# AD_PCB_EXTERNA.net
KiCad netlist of a schematic drawn in Altium Designer
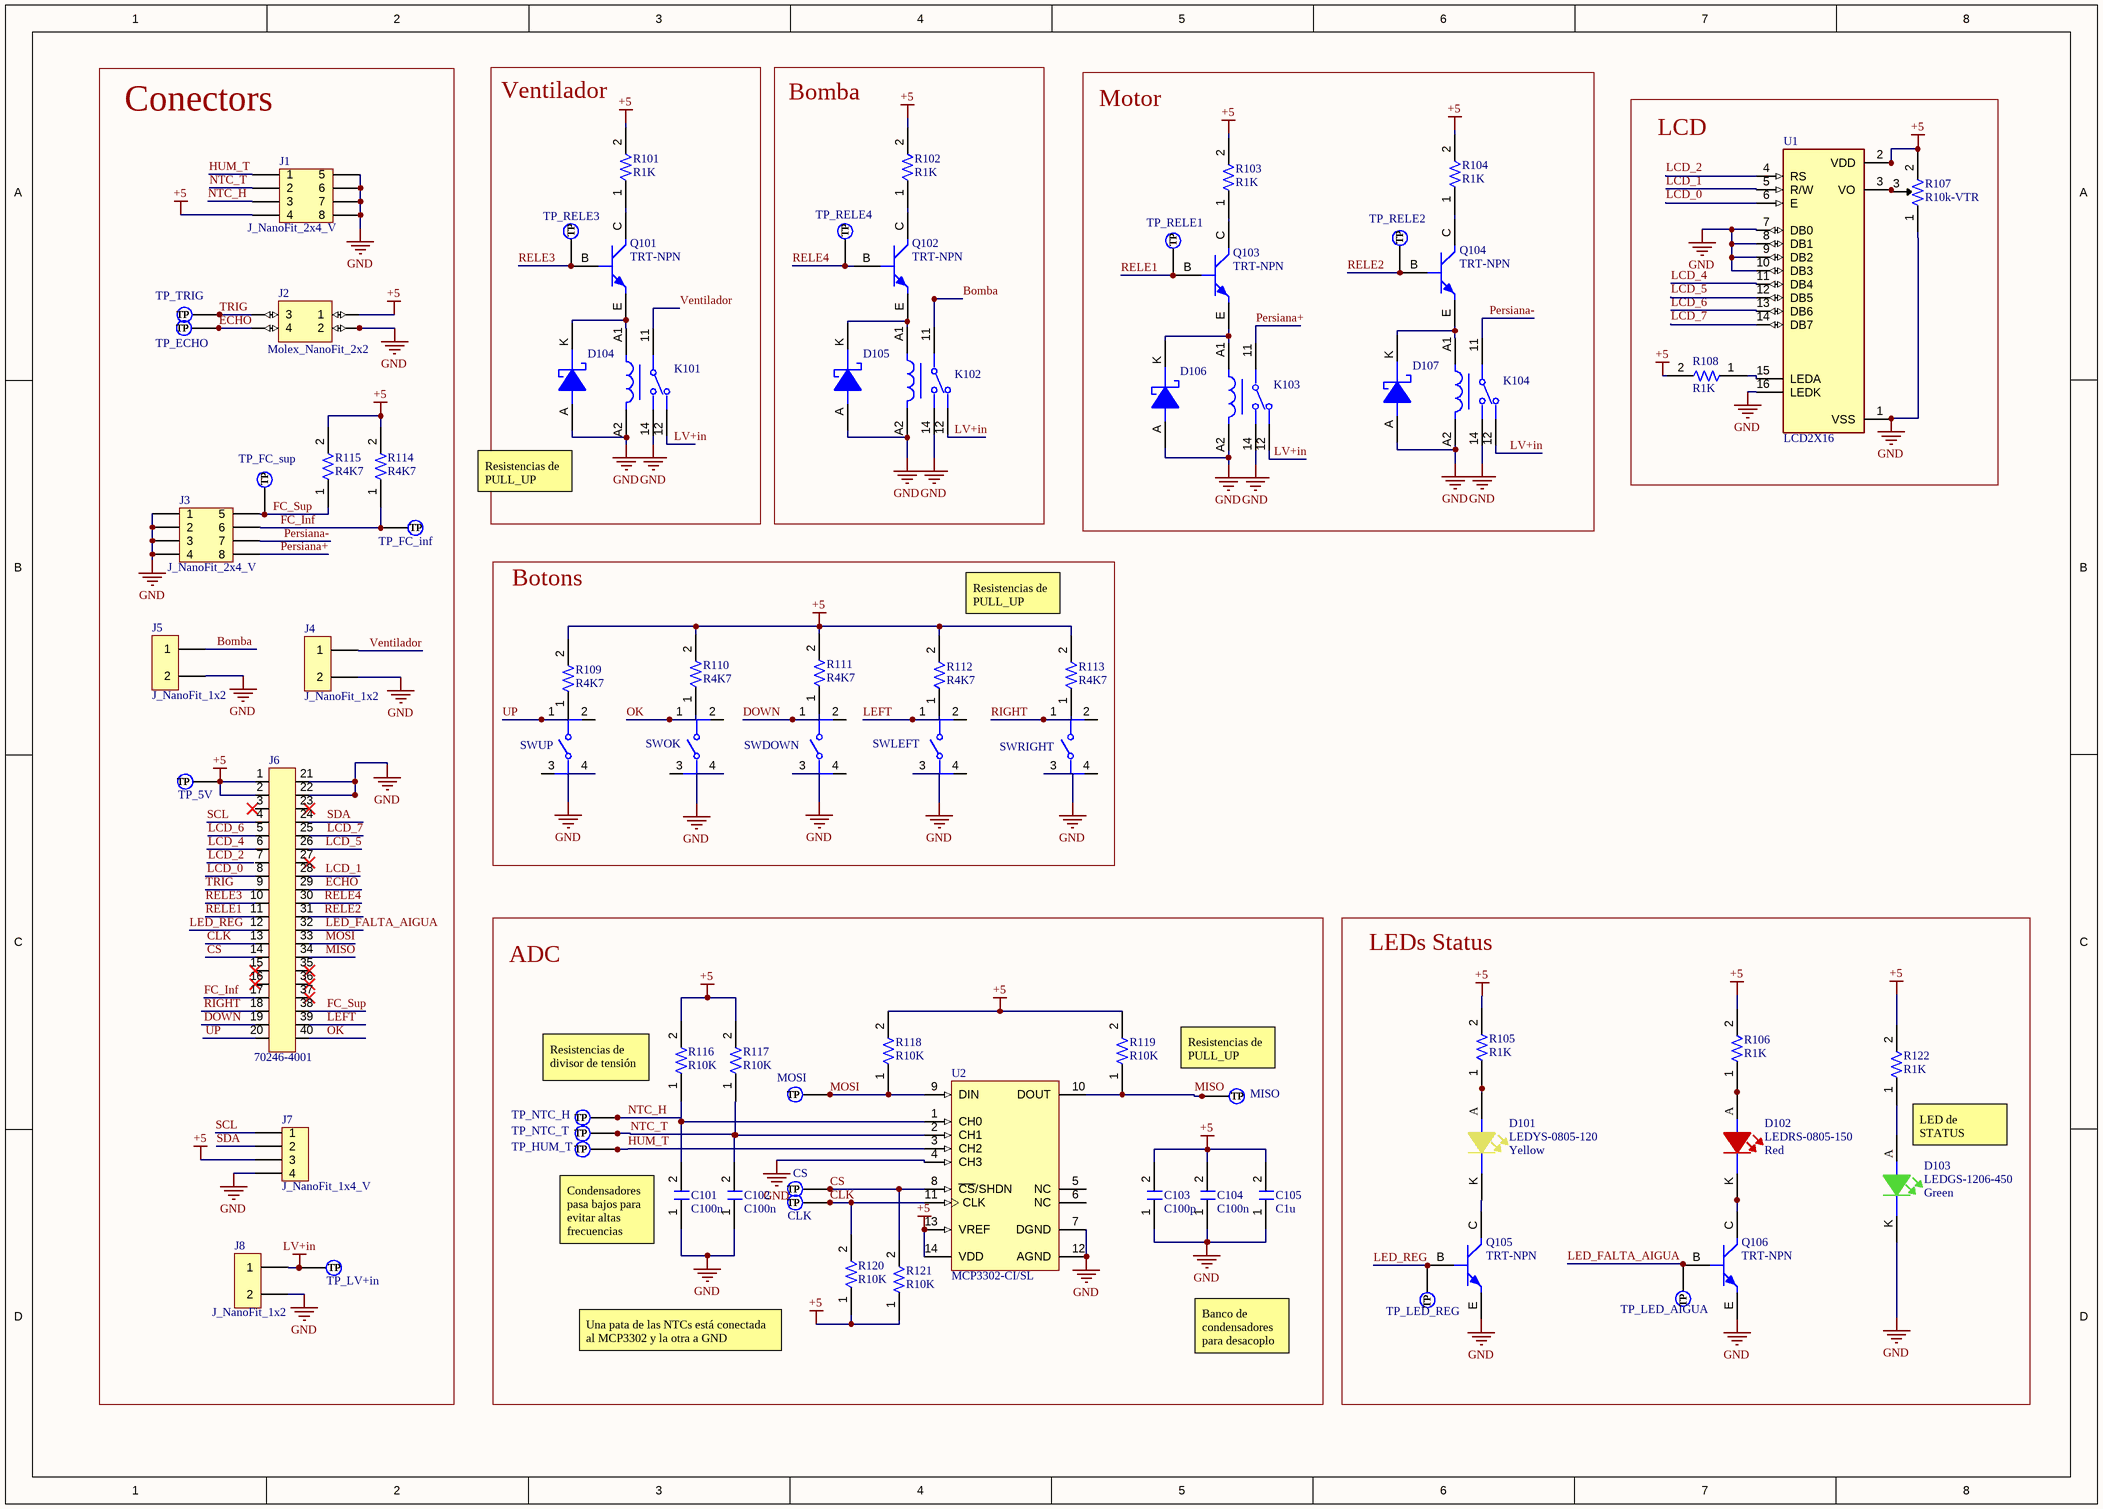
[diagram p0: AD_PCB_EXTERNA.SchDoc]

(export (version "E")
  (design (tool "Eeschema 10.0.6"))
  (components
    (comp (ref "C101")
      (value "C100n")
      (footprint "C0805FNPC-R")
      (description "Cap, 0.1ΜF, 50V, 10%, X7R, 0805")
      (fields (field (name "TOLERANCE") "10%") (field (name ".CREATOR") "DR"))
      (libsource (lib "EMEA- E-Tech Racing- I'Escola d'Enginyeria de Barcelona Est") (part "C100p-50V-0805FNPC-C0G/NP0"))
    )
    (comp (ref "C102")
      (value "C100n")
      (footprint "C0805FNPC-R")
      (description "Cap, 0.1ΜF, 50V, 10%, X7R, 0805")
      (fields (field (name "TOLERANCE") "10%") (field (name ".CREATOR") "DR"))
      (libsource (lib "EMEA- E-Tech Racing- I'Escola d'Enginyeria de Barcelona Est") (part "C100p-50V-0805FNPC-C0G/NP0"))
    )
    (comp (ref "C103")
      (value "C100p")
      (footprint "C0805FNPC-W")
      (fields
        (field (name "MANUFACTURER") "Wurth Electronics")
        (field (name "TOLERANCE") "5%")
        (field (name "MANUFACTURER PART NUMBER") "885012007057")
        (field (name ".CREATOR") "DR")
      )
      (libsource (lib "EMEA- E-Tech Racing- I'Escola d'Enginyeria de Barcelona Est") (part "C100p-50V-0805FNPC-C0G/NP0"))
    )
    (comp (ref "C104")
      (value "C100n")
      (footprint "C0805FNPC-R")
      (description "Cap, 0.1ΜF, 50V, 10%, X7R, 0805")
      (fields (field (name "TOLERANCE") "10%") (field (name ".CREATOR") "DR"))
      (libsource (lib "EMEA- E-Tech Racing- I'Escola d'Enginyeria de Barcelona Est") (part "C100p-50V-0805FNPC-C0G/NP0"))
    )
    (comp (ref "C105")
      (value "C1u")
      (footprint "C0805FNPC-R")
      (fields (field (name "TOLERANCE") "10%") (field (name ".CREATOR") "GP"))
      (libsource (lib "EMEA- E-Tech Racing- I'Escola d'Enginyeria de Barcelona Est") (part "C1u"))
    )
    (comp (ref "CLK")
      (value "TestPoint")
      (footprint "TestPoint")
      (description "Test Point 1x1 mm")
      (fields (field (name ".PCBCHECK") "GP") (field (name ".CREATOR") "GP") (field (name ".SCHCHECK") "GP"))
      (libsource (lib "EMEA- E-Tech Racing- I'Escola d'Enginyeria de Barcelona Est") (part "TestPoint"))
    )
    (comp (ref "CS")
      (value "TestPoint")
      (footprint "TestPoint")
      (description "Test Point 1x1 mm")
      (fields (field (name ".PCBCHECK") "GP") (field (name ".CREATOR") "GP") (field (name ".SCHCHECK") "GP"))
      (libsource (lib "EMEA- E-Tech Racing- I'Escola d'Enginyeria de Barcelona Est") (part "TestPoint"))
    )
    (comp (ref "D101")
      (value "LEDYS-0805-120")
      (footprint "LED_0805_WE")
      (description "2 V Yellow LED 2012 (0805) SMD, Wurth Elektronik WL-SMCW 150080YS75000")
      (fields (field (name "COLOR") "Yellow") (field (name ".CREATOR") "DR"))
      (libsource (lib "EMEA- E-Tech Racing- I'Escola d'Enginyeria de Barcelona Est") (part "LEDYS-3528-260"))
    )
    (comp (ref "D102")
      (value "LEDRS-0805-150")
      (footprint "LED_0805_WE")
      (description "0805(H=0.8mm) 红色 高亮 λD=625nm VF=2V IF=30mA PD=72mW")
      (fields (field (name "COLOR") "Red") (field (name ".CREATOR") "DR"))
      (libsource (lib "EMEA- E-Tech Racing- I'Escola d'Enginyeria de Barcelona Est") (part "LEDRS-1206-1100-Reverse"))
    )
    (comp (ref "D103")
      (value "LEDGS-1206-450")
      (footprint "LED_1206_WE")
      (description "Led, Green, 520 Nm, 3.2 V, 30 Ma, 450 Mcd Rohs Compliant: Yes")
      (fields
        (field (name "COLOR") "Green")
        (field (name "MANUFACTURER") "Wurth Electronics")
        (field (name "MANUFACTURER PART NUMBER") "150120GS75000")
        (field (name ".CREATOR") "GP")
      )
      (libsource (lib "EMEA- E-Tech Racing- I'Escola d'Enginyeria de Barcelona Est") (part "LEDGS-2214-1200"))
    )
    (comp (ref "D104")
      (value "DSC-0.5/30-SOD123")
      (footprint "DSC-SOD123")
      (description "VR=30V IF=500mA 30pF P=410mW")
      (fields (field (name ".CREATOR") "GP"))
      (libsource (lib "EMEA- E-Tech Racing- I'Escola d'Enginyeria de Barcelona Est") (part "DSC-0.5/30-SOD123"))
    )
    (comp (ref "D105")
      (value "DSC-0.5/30-SOD123")
      (footprint "DSC-SOD123")
      (description "VR=30V IF=500mA 30pF P=410mW")
      (fields (field (name ".CREATOR") "GP"))
      (libsource (lib "EMEA- E-Tech Racing- I'Escola d'Enginyeria de Barcelona Est") (part "DSC-0.5/30-SOD123"))
    )
    (comp (ref "D106")
      (value "DSC-0.5/30-SOD123")
      (footprint "DSC-SOD123")
      (description "VR=30V IF=500mA 30pF P=410mW")
      (fields (field (name ".CREATOR") "GP"))
      (libsource (lib "EMEA- E-Tech Racing- I'Escola d'Enginyeria de Barcelona Est") (part "DSC-0.5/30-SOD123"))
    )
    (comp (ref "D107")
      (value "DSC-0.5/30-SOD123")
      (footprint "DSC-SOD123")
      (description "VR=30V IF=500mA 30pF P=410mW")
      (fields (field (name ".CREATOR") "GP"))
      (libsource (lib "EMEA- E-Tech Racing- I'Escola d'Enginyeria de Barcelona Est") (part "DSC-0.5/30-SOD123"))
    )
    (comp (ref "J1")
      (value "J_NanoFit_2x4_V")
      (footprint "J_NanoFit_2x4_V")
      (description "Nano-Fit Conn Power HDR 8 POS 2.5mm Solder ST Thru-Hole 8 Terminal 1 Port Nano-Fit™ Frame")
      (fields (field (name "MANUFACTURER") "Molex") (field (name "MANUFACTURER PART NUMBER") "105310-1108"))
      (libsource (lib "EMEA- E-Tech Racing- I'Escola d'Enginyeria de Barcelona Est") (part "J_NanoFit_2x4_V"))
    )
    (comp (ref "J2")
      (value "Molex_NanoFit_2x2")
      (footprint "J_NanoFit_2x2_V")
      (description "Nano-Fit Vertical Header Through Hole 2.50mm Pitch Dual Row 4 Circuits Tin (Sn) Plating Black")
      (fields
        (field (name "MANUFACTURER") "Molex")
        (field (name "MANUFACTURER PART NUMBER") "1053141104")
        (field (name ".CREATOR") "GP")
      )
      (libsource (lib "EMEA- E-Tech Racing- I'Escola d'Enginyeria de Barcelona Est") (part "J_Nanofit_2x2"))
    )
    (comp (ref "J3")
      (value "J_NanoFit_2x4_V")
      (footprint "J_NanoFit_2x4_V")
      (description "Nano-Fit Conn Power HDR 8 POS 2.5mm Solder ST Thru-Hole 8 Terminal 1 Port Nano-Fit™ Frame")
      (fields (field (name "MANUFACTURER") "Molex") (field (name "MANUFACTURER PART NUMBER") "105310-1108"))
      (libsource (lib "EMEA- E-Tech Racing- I'Escola d'Enginyeria de Barcelona Est") (part "J_NanoFit_2x4_V"))
    )
    (comp (ref "J4")
      (value "J_NanoFit_1x2")
      (footprint "FP-105309-1102-MFG")
      (description "Conn HDR 2 POS 2.5mm Solder ST Thru-Hole 2 Terminal 1 Port Nano-Fit Tray")
      (libsource (lib "EMEA- E-Tech Racing- I'Escola d'Enginyeria de Barcelona Est") (part "Molex Nano-Fit"))
    )
    (comp (ref "J5")
      (value "J_NanoFit_1x2")
      (footprint "FP-105309-1102-MFG")
      (description "Conn HDR 2 POS 2.5mm Solder ST Thru-Hole 2 Terminal 1 Port Nano-Fit Tray")
      (libsource (lib "EMEA- E-Tech Racing- I'Escola d'Enginyeria de Barcelona Est") (part "Molex Nano-Fit"))
    )
    (comp (ref "J6")
      (value "70246-4001")
      (footprint "CONN_7024640xx_MOL")
      (libsource (lib "EMEA- E-Tech Racing- I'Escola d'Enginyeria de Barcelona Est") (part "70246-4001-Symbol-1"))
    )
    (comp (ref "J7")
      (value "J_NanoFit_1x4_V")
      (footprint "J_NanoFit_1x4_V")
      (description "Nano-Fit Vertical Header Through Hole 2.50mm Pitch Single Row 4 Circuits with Kinked Pins 0.38")
      (fields (field (name ".CREATOR") "DO"))
      (libsource (lib "EMEA- E-Tech Racing- I'Escola d'Enginyeria de Barcelona Est") (part "J_NanoFit_1x4_V_W"))
    )
    (comp (ref "J8")
      (value "J_NanoFit_1x2")
      (footprint "FP-105309-1102-MFG")
      (description "Conn HDR 2 POS 2.5mm Solder ST Thru-Hole 2 Terminal 1 Port Nano-Fit Tray")
      (libsource (lib "EMEA- E-Tech Racing- I'Escola d'Enginyeria de Barcelona Est") (part "Molex Nano-Fit"))
    )
    (comp (ref "K101")
      (value "Relay_RZ01-1C4-D005")
      (footprint "FP-1415899-7-MFG")
      (libsource (lib "EMEA- E-Tech Racing- I'Escola d'Enginyeria de Barcelona Est") (part "5e088b4eeede5deee4b60b77e0ea9e2"))
    )
    (comp (ref "K102")
      (value "Relay_RZ01-1C4-D005")
      (footprint "FP-1415899-7-MFG")
      (libsource (lib "EMEA- E-Tech Racing- I'Escola d'Enginyeria de Barcelona Est") (part "5e088b4eeede5deee4b60b77e0ea9e2"))
    )
    (comp (ref "K103")
      (value "Relay_RZ01-1C4-D005")
      (footprint "FP-1415899-7-MFG")
      (libsource (lib "EMEA- E-Tech Racing- I'Escola d'Enginyeria de Barcelona Est") (part "5e088b4eeede5deee4b60b77e0ea9e2"))
    )
    (comp (ref "K104")
      (value "Relay_RZ01-1C4-D005")
      (footprint "FP-1415899-7-MFG")
      (libsource (lib "EMEA- E-Tech Racing- I'Escola d'Enginyeria de Barcelona Est") (part "5e088b4eeede5deee4b60b77e0ea9e2"))
    )
    (comp (ref "MISO")
      (value "TestPoint")
      (footprint "TestPoint")
      (description "Test Point 1x1 mm")
      (fields (field (name ".PCBCHECK") "GP") (field (name ".CREATOR") "GP") (field (name ".SCHCHECK") "GP"))
      (libsource (lib "EMEA- E-Tech Racing- I'Escola d'Enginyeria de Barcelona Est") (part "TestPoint"))
    )
    (comp (ref "MOSI")
      (value "TestPoint")
      (footprint "TestPoint")
      (description "Test Point 1x1 mm")
      (fields (field (name ".PCBCHECK") "GP") (field (name ".CREATOR") "GP") (field (name ".SCHCHECK") "GP"))
      (libsource (lib "EMEA- E-Tech Racing- I'Escola d'Enginyeria de Barcelona Est") (part "TestPoint"))
    )
    (comp (ref "Q101")
      (value "TRT-NPN")
      (footprint "TRT-NPN-0.5/45-SOT23")
      (description "ON Semi BC817-25LT1G NPN Bipolar Transistor; 0.5 A; 45 V; 3-Pin SOT-23")
      (fields (field (name ".CREATOR") "GP"))
      (libsource (lib "EMEA- E-Tech Racing- I'Escola d'Enginyeria de Barcelona Est") (part "TRT-NPN-0.5/45-SOT23"))
    )
    (comp (ref "Q102")
      (value "TRT-NPN")
      (footprint "TRT-NPN-0.5/45-SOT23")
      (description "ON Semi BC817-25LT1G NPN Bipolar Transistor; 0.5 A; 45 V; 3-Pin SOT-23")
      (fields (field (name ".CREATOR") "GP"))
      (libsource (lib "EMEA- E-Tech Racing- I'Escola d'Enginyeria de Barcelona Est") (part "TRT-NPN-0.5/45-SOT23"))
    )
    (comp (ref "Q103")
      (value "TRT-NPN")
      (footprint "TRT-NPN-0.5/45-SOT23")
      (description "ON Semi BC817-25LT1G NPN Bipolar Transistor; 0.5 A; 45 V; 3-Pin SOT-23")
      (fields (field (name ".CREATOR") "GP"))
      (libsource (lib "EMEA- E-Tech Racing- I'Escola d'Enginyeria de Barcelona Est") (part "TRT-NPN-0.5/45-SOT23"))
    )
    (comp (ref "Q104")
      (value "TRT-NPN")
      (footprint "TRT-NPN-0.5/45-SOT23")
      (description "ON Semi BC817-25LT1G NPN Bipolar Transistor; 0.5 A; 45 V; 3-Pin SOT-23")
      (fields (field (name ".CREATOR") "GP"))
      (libsource (lib "EMEA- E-Tech Racing- I'Escola d'Enginyeria de Barcelona Est") (part "TRT-NPN-0.5/45-SOT23"))
    )
    (comp (ref "Q105")
      (value "TRT-NPN")
      (footprint "TRT-NPN-0.5/45-SOT23")
      (description "ON Semi BC817-25LT1G NPN Bipolar Transistor; 0.5 A; 45 V; 3-Pin SOT-23")
      (fields (field (name ".CREATOR") "GP"))
      (libsource (lib "EMEA- E-Tech Racing- I'Escola d'Enginyeria de Barcelona Est") (part "TRT-NPN-0.5/45-SOT23"))
    )
    (comp (ref "Q106")
      (value "TRT-NPN")
      (footprint "TRT-NPN-0.5/45-SOT23")
      (description "ON Semi BC817-25LT1G NPN Bipolar Transistor; 0.5 A; 45 V; 3-Pin SOT-23")
      (fields (field (name ".CREATOR") "GP"))
      (libsource (lib "EMEA- E-Tech Racing- I'Escola d'Enginyeria de Barcelona Est") (part "TRT-NPN-0.5/45-SOT23"))
    )
    (comp (ref "R101")
      (value "R1K")
      (footprint "0805")
      (description "Fixed Resistor, Thin Film, 0.125W, 1000ohm, 150V, 0.1% +/-Tol, 15ppm/Cel, Surface Mount, 0805")
      (fields (field (name "TOLERANCE") "0.1%") (field (name "POWER") "125mW"))
      (libsource (lib "EMEA- E-Tech Racing- I'Escola d'Enginyeria de Barcelona Est") (part "CRCW08055K30FKTA"))
    )
    (comp (ref "R102")
      (value "R1K")
      (footprint "0805")
      (description "Fixed Resistor, Thin Film, 0.125W, 1000ohm, 150V, 0.1% +/-Tol, 15ppm/Cel, Surface Mount, 0805")
      (fields (field (name "TOLERANCE") "0.1%") (field (name "POWER") "125mW"))
      (libsource (lib "EMEA- E-Tech Racing- I'Escola d'Enginyeria de Barcelona Est") (part "CRCW08055K30FKTA"))
    )
    (comp (ref "R103")
      (value "R1K")
      (footprint "0805")
      (description "Fixed Resistor, Thin Film, 0.125W, 1000ohm, 150V, 0.1% +/-Tol, 15ppm/Cel, Surface Mount, 0805")
      (fields (field (name "TOLERANCE") "0.1%") (field (name "POWER") "125mW"))
      (libsource (lib "EMEA- E-Tech Racing- I'Escola d'Enginyeria de Barcelona Est") (part "CRCW08055K30FKTA"))
    )
    (comp (ref "R104")
      (value "R1K")
      (footprint "0805")
      (description "Fixed Resistor, Thin Film, 0.125W, 1000ohm, 150V, 0.1% +/-Tol, 15ppm/Cel, Surface Mount, 0805")
      (fields (field (name "TOLERANCE") "0.1%") (field (name "POWER") "125mW"))
      (libsource (lib "EMEA- E-Tech Racing- I'Escola d'Enginyeria de Barcelona Est") (part "CRCW08055K30FKTA"))
    )
    (comp (ref "R105")
      (value "R1K")
      (footprint "0805")
      (description "Fixed Resistor, Thin Film, 0.125W, 1000ohm, 150V, 0.1% +/-Tol, 15ppm/Cel, Surface Mount, 0805")
      (fields (field (name "TOLERANCE") "0.1%") (field (name "POWER") "125mW"))
      (libsource (lib "EMEA- E-Tech Racing- I'Escola d'Enginyeria de Barcelona Est") (part "CRCW08055K30FKTA"))
    )
    (comp (ref "R106")
      (value "R1K")
      (footprint "0805")
      (description "Fixed Resistor, Thin Film, 0.125W, 1000ohm, 150V, 0.1% +/-Tol, 15ppm/Cel, Surface Mount, 0805")
      (fields (field (name "TOLERANCE") "0.1%") (field (name "POWER") "125mW"))
      (libsource (lib "EMEA- E-Tech Racing- I'Escola d'Enginyeria de Barcelona Est") (part "CRCW08055K30FKTA"))
    )
    (comp (ref "R107")
      (value "R10k-VTR")
      (footprint "R10k-VTR")
      (description "Trimmer, Cermet, Rest 10 Kilohms, PCB, 25 Turns, Pwr-Rtg 0.5W, 3296 Series")
      (fields
        (field (name "MANUFACTURER PART NUMBER") "3296W-1-103LF")
        (field (name "TOLERANCE") "10%")
        (field (name ".CREATOR") "DO")
      )
      (libsource (lib "EMEA- E-Tech Racing- I'Escola d'Enginyeria de Barcelona Est") (part "R10k-VTR_RM065"))
    )
    (comp (ref "R108")
      (value "R1K")
      (footprint "0805")
      (description "Fixed Resistor, Thin Film, 0.125W, 1000ohm, 150V, 0.1% +/-Tol, 15ppm/Cel, Surface Mount, 0805")
      (fields (field (name "TOLERANCE") "0.1%") (field (name "POWER") "125mW"))
      (libsource (lib "EMEA- E-Tech Racing- I'Escola d'Enginyeria de Barcelona Est") (part "CRCW08055K30FKTA"))
    )
    (comp (ref "R109")
      (value "R4K7")
      (footprint "0805")
      (description "Fixed Resistor, Thin Film, 0.125W, 1000ohm, 150V, 0.1% +/-Tol, 15ppm/Cel, Surface Mount, 0805")
      (fields (field (name "TOLERANCE") "0.1%") (field (name "POWER") "125mW"))
      (libsource (lib "EMEA- E-Tech Racing- I'Escola d'Enginyeria de Barcelona Est") (part "CRCW08055K30FKTA"))
    )
    (comp (ref "R110")
      (value "R4K7")
      (footprint "0805")
      (description "Fixed Resistor, Thin Film, 0.125W, 1000ohm, 150V, 0.1% +/-Tol, 15ppm/Cel, Surface Mount, 0805")
      (fields (field (name "TOLERANCE") "0.1%") (field (name "POWER") "125mW"))
      (libsource (lib "EMEA- E-Tech Racing- I'Escola d'Enginyeria de Barcelona Est") (part "CRCW08055K30FKTA"))
    )
    (comp (ref "R111")
      (value "R4K7")
      (footprint "0805")
      (description "Fixed Resistor, Thin Film, 0.125W, 1000ohm, 150V, 0.1% +/-Tol, 15ppm/Cel, Surface Mount, 0805")
      (fields (field (name "TOLERANCE") "0.1%") (field (name "POWER") "125mW"))
      (libsource (lib "EMEA- E-Tech Racing- I'Escola d'Enginyeria de Barcelona Est") (part "CRCW08055K30FKTA"))
    )
    (comp (ref "R112")
      (value "R4K7")
      (footprint "0805")
      (description "Fixed Resistor, Thin Film, 0.125W, 1000ohm, 150V, 0.1% +/-Tol, 15ppm/Cel, Surface Mount, 0805")
      (fields (field (name "TOLERANCE") "0.1%") (field (name "POWER") "125mW"))
      (libsource (lib "EMEA- E-Tech Racing- I'Escola d'Enginyeria de Barcelona Est") (part "CRCW08055K30FKTA"))
    )
    (comp (ref "R113")
      (value "R4K7")
      (footprint "0805")
      (description "Fixed Resistor, Thin Film, 0.125W, 1000ohm, 150V, 0.1% +/-Tol, 15ppm/Cel, Surface Mount, 0805")
      (fields (field (name "TOLERANCE") "0.1%") (field (name "POWER") "125mW"))
      (libsource (lib "EMEA- E-Tech Racing- I'Escola d'Enginyeria de Barcelona Est") (part "CRCW08055K30FKTA"))
    )
    (comp (ref "R114")
      (value "R4K7")
      (footprint "0805")
      (description "Fixed Resistor, Thin Film, 0.125W, 1000ohm, 150V, 0.1% +/-Tol, 15ppm/Cel, Surface Mount, 0805")
      (fields (field (name "TOLERANCE") "0.1%") (field (name "POWER") "125mW"))
      (libsource (lib "EMEA- E-Tech Racing- I'Escola d'Enginyeria de Barcelona Est") (part "CRCW08055K30FKTA"))
    )
    (comp (ref "R115")
      (value "R4K7")
      (footprint "0805")
      (description "Fixed Resistor, Thin Film, 0.125W, 1000ohm, 150V, 0.1% +/-Tol, 15ppm/Cel, Surface Mount, 0805")
      (fields (field (name "TOLERANCE") "0.1%") (field (name "POWER") "125mW"))
      (libsource (lib "EMEA- E-Tech Racing- I'Escola d'Enginyeria de Barcelona Est") (part "CRCW08055K30FKTA"))
    )
    (comp (ref "R116")
      (value "R10K")
      (footprint "0805")
      (description "Fixed Resistor, Thin Film, 0.125W, 1000ohm, 150V, 0.1% +/-Tol, 15ppm/Cel, Surface Mount, 0805")
      (fields (field (name "TOLERANCE") "0.1%") (field (name "POWER") "125mW"))
      (libsource (lib "EMEA- E-Tech Racing- I'Escola d'Enginyeria de Barcelona Est") (part "CRCW08055K30FKTA"))
    )
    (comp (ref "R117")
      (value "R10K")
      (footprint "0805")
      (description "Fixed Resistor, Thin Film, 0.125W, 1000ohm, 150V, 0.1% +/-Tol, 15ppm/Cel, Surface Mount, 0805")
      (fields (field (name "TOLERANCE") "0.1%") (field (name "POWER") "125mW"))
      (libsource (lib "EMEA- E-Tech Racing- I'Escola d'Enginyeria de Barcelona Est") (part "CRCW08055K30FKTA"))
    )
    (comp (ref "R118")
      (value "R10K")
      (footprint "0805")
      (description "Fixed Resistor, Thin Film, 0.125W, 1000ohm, 150V, 0.1% +/-Tol, 15ppm/Cel, Surface Mount, 0805")
      (fields (field (name "TOLERANCE") "0.1%") (field (name "POWER") "125mW"))
      (libsource (lib "EMEA- E-Tech Racing- I'Escola d'Enginyeria de Barcelona Est") (part "CRCW08055K30FKTA"))
    )
    (comp (ref "R119")
      (value "R10K")
      (footprint "0805")
      (description "Fixed Resistor, Thin Film, 0.125W, 1000ohm, 150V, 0.1% +/-Tol, 15ppm/Cel, Surface Mount, 0805")
      (fields (field (name "TOLERANCE") "0.1%") (field (name "POWER") "125mW"))
      (libsource (lib "EMEA- E-Tech Racing- I'Escola d'Enginyeria de Barcelona Est") (part "CRCW08055K30FKTA"))
    )
    (comp (ref "R120")
      (value "R10K")
      (footprint "0805")
      (description "Fixed Resistor, Thin Film, 0.125W, 1000ohm, 150V, 0.1% +/-Tol, 15ppm/Cel, Surface Mount, 0805")
      (fields (field (name "TOLERANCE") "0.1%") (field (name "POWER") "125mW"))
      (libsource (lib "EMEA- E-Tech Racing- I'Escola d'Enginyeria de Barcelona Est") (part "CRCW08055K30FKTA"))
    )
    (comp (ref "R121")
      (value "R10K")
      (footprint "0805")
      (description "Fixed Resistor, Thin Film, 0.125W, 1000ohm, 150V, 0.1% +/-Tol, 15ppm/Cel, Surface Mount, 0805")
      (fields (field (name "TOLERANCE") "0.1%") (field (name "POWER") "125mW"))
      (libsource (lib "EMEA- E-Tech Racing- I'Escola d'Enginyeria de Barcelona Est") (part "CRCW08055K30FKTA"))
    )
    (comp (ref "R122")
      (value "R1K")
      (footprint "0805")
      (description "Fixed Resistor, Thin Film, 0.125W, 1000ohm, 150V, 0.1% +/-Tol, 15ppm/Cel, Surface Mount, 0805")
      (fields (field (name "TOLERANCE") "0.1%") (field (name "POWER") "125mW"))
      (libsource (lib "EMEA- E-Tech Racing- I'Escola d'Enginyeria de Barcelona Est") (part "CRCW08055K30FKTA"))
    )
    (comp (ref "SWDOWN")
      (value "tact_switch")
      (footprint "FP-PTS647SK38SMTR2LFS-MFG")
      (libsource (lib "EMEA- E-Tech Racing- I'Escola d'Enginyeria de Barcelona Est") (part "1adf0dd01260c80cf25a44bfd6b99ba"))
    )
    (comp (ref "SWLEFT")
      (value "tact_switch")
      (footprint "FP-PTS647SK38SMTR2LFS-MFG")
      (libsource (lib "EMEA- E-Tech Racing- I'Escola d'Enginyeria de Barcelona Est") (part "1adf0dd01260c80cf25a44bfd6b99ba"))
    )
    (comp (ref "SWOK")
      (value "tact_switch")
      (footprint "FP-PTS647SK38SMTR2LFS-MFG")
      (libsource (lib "EMEA- E-Tech Racing- I'Escola d'Enginyeria de Barcelona Est") (part "1adf0dd01260c80cf25a44bfd6b99ba"))
    )
    (comp (ref "SWRIGHT")
      (value "tact_switch")
      (footprint "FP-PTS647SK38SMTR2LFS-MFG")
      (libsource (lib "EMEA- E-Tech Racing- I'Escola d'Enginyeria de Barcelona Est") (part "1adf0dd01260c80cf25a44bfd6b99ba"))
    )
    (comp (ref "SWUP")
      (value "tact_switch")
      (footprint "FP-PTS647SK38SMTR2LFS-MFG")
      (libsource (lib "EMEA- E-Tech Racing- I'Escola d'Enginyeria de Barcelona Est") (part "1adf0dd01260c80cf25a44bfd6b99ba"))
    )
    (comp (ref "TP_5V")
      (value "TestPoint")
      (footprint "TestPoint")
      (description "Test Point 1x1 mm")
      (fields (field (name ".PCBCHECK") "GP") (field (name ".CREATOR") "GP") (field (name ".SCHCHECK") "GP"))
      (libsource (lib "EMEA- E-Tech Racing- I'Escola d'Enginyeria de Barcelona Est") (part "TestPoint"))
    )
    (comp (ref "TP_ECHO")
      (value "TestPoint")
      (footprint "TestPoint")
      (description "Test Point 1x1 mm")
      (fields (field (name ".PCBCHECK") "GP") (field (name ".CREATOR") "GP") (field (name ".SCHCHECK") "GP"))
      (libsource (lib "EMEA- E-Tech Racing- I'Escola d'Enginyeria de Barcelona Est") (part "TestPoint"))
    )
    (comp (ref "TP_FC_inf")
      (value "TestPoint")
      (footprint "TestPoint")
      (description "Test Point 1x1 mm")
      (fields (field (name ".PCBCHECK") "GP") (field (name ".CREATOR") "GP") (field (name ".SCHCHECK") "GP"))
      (libsource (lib "EMEA- E-Tech Racing- I'Escola d'Enginyeria de Barcelona Est") (part "TestPoint"))
    )
    (comp (ref "TP_FC_sup")
      (value "TestPoint")
      (footprint "TestPoint")
      (description "Test Point 1x1 mm")
      (fields (field (name ".PCBCHECK") "GP") (field (name ".CREATOR") "GP") (field (name ".SCHCHECK") "GP"))
      (libsource (lib "EMEA- E-Tech Racing- I'Escola d'Enginyeria de Barcelona Est") (part "TestPoint"))
    )
    (comp (ref "TP_HUM_T")
      (value "TestPoint")
      (footprint "TestPoint")
      (description "Test Point 1x1 mm")
      (fields (field (name ".PCBCHECK") "GP") (field (name ".CREATOR") "GP") (field (name ".SCHCHECK") "GP"))
      (libsource (lib "EMEA- E-Tech Racing- I'Escola d'Enginyeria de Barcelona Est") (part "TestPoint"))
    )
    (comp (ref "TP_LED_AIGUA")
      (value "TestPoint")
      (footprint "TestPoint")
      (description "Test Point 1x1 mm")
      (fields (field (name ".PCBCHECK") "GP") (field (name ".CREATOR") "GP") (field (name ".SCHCHECK") "GP"))
      (libsource (lib "EMEA- E-Tech Racing- I'Escola d'Enginyeria de Barcelona Est") (part "TestPoint"))
    )
    (comp (ref "TP_LED_REG")
      (value "TestPoint")
      (footprint "TestPoint")
      (description "Test Point 1x1 mm")
      (fields (field (name ".PCBCHECK") "GP") (field (name ".CREATOR") "GP") (field (name ".SCHCHECK") "GP"))
      (libsource (lib "EMEA- E-Tech Racing- I'Escola d'Enginyeria de Barcelona Est") (part "TestPoint"))
    )
    (comp (ref "TP_LV+in")
      (value "TestPoint")
      (footprint "TestPoint")
      (description "Test Point 1x1 mm")
      (fields (field (name ".PCBCHECK") "GP") (field (name ".CREATOR") "GP") (field (name ".SCHCHECK") "GP"))
      (libsource (lib "EMEA- E-Tech Racing- I'Escola d'Enginyeria de Barcelona Est") (part "TestPoint"))
    )
    (comp (ref "TP_NTC_H")
      (value "TestPoint")
      (footprint "TestPoint")
      (description "Test Point 1x1 mm")
      (fields (field (name ".PCBCHECK") "GP") (field (name ".CREATOR") "GP") (field (name ".SCHCHECK") "GP"))
      (libsource (lib "EMEA- E-Tech Racing- I'Escola d'Enginyeria de Barcelona Est") (part "TestPoint"))
    )
    (comp (ref "TP_NTC_T")
      (value "TestPoint")
      (footprint "TestPoint")
      (description "Test Point 1x1 mm")
      (fields (field (name ".PCBCHECK") "GP") (field (name ".CREATOR") "GP") (field (name ".SCHCHECK") "GP"))
      (libsource (lib "EMEA- E-Tech Racing- I'Escola d'Enginyeria de Barcelona Est") (part "TestPoint"))
    )
    (comp (ref "TP_RELE1")
      (value "TestPoint")
      (footprint "TestPoint")
      (description "Test Point 1x1 mm")
      (fields (field (name ".PCBCHECK") "GP") (field (name ".CREATOR") "GP") (field (name ".SCHCHECK") "GP"))
      (libsource (lib "EMEA- E-Tech Racing- I'Escola d'Enginyeria de Barcelona Est") (part "TestPoint"))
    )
    (comp (ref "TP_RELE2")
      (value "TestPoint")
      (footprint "TestPoint")
      (description "Test Point 1x1 mm")
      (fields (field (name ".PCBCHECK") "GP") (field (name ".CREATOR") "GP") (field (name ".SCHCHECK") "GP"))
      (libsource (lib "EMEA- E-Tech Racing- I'Escola d'Enginyeria de Barcelona Est") (part "TestPoint"))
    )
    (comp (ref "TP_RELE3")
      (value "TestPoint")
      (footprint "TestPoint")
      (description "Test Point 1x1 mm")
      (fields (field (name ".PCBCHECK") "GP") (field (name ".CREATOR") "GP") (field (name ".SCHCHECK") "GP"))
      (libsource (lib "EMEA- E-Tech Racing- I'Escola d'Enginyeria de Barcelona Est") (part "TestPoint"))
    )
    (comp (ref "TP_RELE4")
      (value "TestPoint")
      (footprint "TestPoint")
      (description "Test Point 1x1 mm")
      (fields (field (name ".PCBCHECK") "GP") (field (name ".CREATOR") "GP") (field (name ".SCHCHECK") "GP"))
      (libsource (lib "EMEA- E-Tech Racing- I'Escola d'Enginyeria de Barcelona Est") (part "TestPoint"))
    )
    (comp (ref "TP_TRIG")
      (value "TestPoint")
      (footprint "TestPoint")
      (description "Test Point 1x1 mm")
      (fields (field (name ".PCBCHECK") "GP") (field (name ".CREATOR") "GP") (field (name ".SCHCHECK") "GP"))
      (libsource (lib "EMEA- E-Tech Racing- I'Escola d'Enginyeria de Barcelona Est") (part "TestPoint"))
    )
    (comp (ref "U1")
      (value "LCD2X16")
      (footprint "LCD_LCD2X16")
      (description "Display; Display: LCD 2x16 characters (blue backlight)")
      (fields (field (name "MF") "mikroElektronika") (field (name "MP") "LCD 2X16"))
      (libsource (lib "EMEA- E-Tech Racing- I'Escola d'Enginyeria de Barcelona Est") (part "LCD2X16"))
    )
    (comp (ref "U2")
      (value "MCP3302-CI/SL")
      (footprint "SOIC-SL14_L")
      (description "ADC, Successive Approximation, 13-Bit, 1 Func, 4 Channel, Serial Access, PDSO14")
      (libsource (lib "EMEA- E-Tech Racing- I'Escola d'Enginyeria de Barcelona Est") (part "CON-ADC-MCP3004-14"))
    )
  )
  (nets
    (net (code "1") (name "+5") (class "Default")
      (node (ref "C103") (pin "2") (pinfunction "2_2") (pintype "passive"))
      (node (ref "C104") (pin "2") (pinfunction "2_2") (pintype "passive"))
      (node (ref "C105") (pin "2") (pinfunction "2_2") (pintype "passive"))
      (node (ref "J1") (pin "4") (pinfunction "4_4") (pintype "passive"))
      (node (ref "J2") (pin "1") (pinfunction "1_1") (pintype "bidirectional"))
      (node (ref "J6") (pin "1") (pintype "bidirectional"))
      (node (ref "J6") (pin "2") (pintype "bidirectional"))
      (node (ref "J7") (pin "3") (pinfunction "3_3") (pintype "passive"))
      (node (ref "R101") (pin "2") (pinfunction "2_2") (pintype "passive"))
      (node (ref "R102") (pin "2") (pinfunction "2_2") (pintype "passive"))
      (node (ref "R103") (pin "2") (pinfunction "2_2") (pintype "passive"))
      (node (ref "R104") (pin "2") (pinfunction "2_2") (pintype "passive"))
      (node (ref "R105") (pin "2") (pinfunction "2_2") (pintype "passive"))
      (node (ref "R106") (pin "2") (pinfunction "2_2") (pintype "passive"))
      (node (ref "R107") (pin "2") (pinfunction "2_2") (pintype "passive"))
      (node (ref "R108") (pin "2") (pinfunction "2_2") (pintype "passive"))
      (node (ref "R109") (pin "2") (pinfunction "2_2") (pintype "passive"))
      (node (ref "R110") (pin "2") (pinfunction "2_2") (pintype "passive"))
      (node (ref "R111") (pin "2") (pinfunction "2_2") (pintype "passive"))
      (node (ref "R112") (pin "2") (pinfunction "2_2") (pintype "passive"))
      (node (ref "R113") (pin "2") (pinfunction "2_2") (pintype "passive"))
      (node (ref "R114") (pin "2") (pinfunction "2_2") (pintype "passive"))
      (node (ref "R115") (pin "2") (pinfunction "2_2") (pintype "passive"))
      (node (ref "R116") (pin "2") (pinfunction "2_2") (pintype "passive"))
      (node (ref "R117") (pin "2") (pinfunction "2_2") (pintype "passive"))
      (node (ref "R118") (pin "2") (pinfunction "2_2") (pintype "passive"))
      (node (ref "R119") (pin "2") (pinfunction "2_2") (pintype "passive"))
      (node (ref "R120") (pin "1") (pinfunction "1_1") (pintype "passive"))
      (node (ref "R121") (pin "1") (pinfunction "1_1") (pintype "passive"))
      (node (ref "R122") (pin "2") (pinfunction "2_2") (pintype "passive"))
      (node (ref "TP_5V") (pin "1") (pinfunction "TP_1") (pintype "passive"))
      (node (ref "U1") (pin "2") (pinfunction "VDD_2") (pintype "power_in"))
      (node (ref "U2") (pin "13") (pinfunction "VREF_13") (pintype "input"))
      (node (ref "U2") (pin "14") (pinfunction "VDD_14") (pintype "power_in"))
    )
    (net (code "2") (name "/Bomba") (class "Default")
      (node (ref "J5") (pin "1") (pinfunction "1_1") (pintype "passive"))
      (node (ref "K102") (pin "11") (pinfunction "11_11") (pintype "passive"))
    )
    (net (code "3") (name "/CLK") (class "Default")
      (node (ref "CLK") (pin "1") (pinfunction "TP_1") (pintype "passive"))
      (node (ref "J6") (pin "13") (pintype "bidirectional"))
      (node (ref "R120") (pin "2") (pinfunction "2_2") (pintype "passive"))
      (node (ref "U2") (pin "11") (pinfunction "CLK_11") (pintype "input"))
    )
    (net (code "4") (name "/CS") (class "Default")
      (node (ref "CS") (pin "1") (pinfunction "TP_1") (pintype "passive"))
      (node (ref "J6") (pin "14") (pintype "bidirectional"))
      (node (ref "R121") (pin "2") (pinfunction "2_2") (pintype "passive"))
      (node (ref "U2") (pin "8") (pinfunction "~{CS}/SHDN_8") (pintype "input"))
    )
    (net (code "5") (name "/DOWN") (class "Default")
      (node (ref "J6") (pin "19") (pintype "bidirectional"))
      (node (ref "R111") (pin "1") (pinfunction "1_1") (pintype "passive"))
      (node (ref "SWDOWN") (pin "1") (pinfunction "1_1") (pintype "passive"))
    )
    (net (code "6") (name "/ECHO") (class "Default")
      (node (ref "J2") (pin "4") (pinfunction "4_4") (pintype "bidirectional"))
      (node (ref "J6") (pin "29") (pintype "bidirectional"))
      (node (ref "TP_ECHO") (pin "1") (pinfunction "TP_1") (pintype "passive"))
    )
    (net (code "7") (name "/FC_Inf") (class "Default")
      (node (ref "J3") (pin "6") (pinfunction "6_6") (pintype "passive"))
      (node (ref "J6") (pin "17") (pintype "bidirectional"))
      (node (ref "R114") (pin "1") (pinfunction "1_1") (pintype "passive"))
      (node (ref "TP_FC_inf") (pin "1") (pinfunction "TP_1") (pintype "passive"))
    )
    (net (code "8") (name "/FC_Sup") (class "Default")
      (node (ref "J3") (pin "5") (pinfunction "5_5") (pintype "passive"))
      (node (ref "J6") (pin "38") (pintype "bidirectional"))
      (node (ref "R115") (pin "1") (pinfunction "1_1") (pintype "passive"))
      (node (ref "TP_FC_sup") (pin "1") (pinfunction "TP_1") (pintype "passive"))
    )
    (net (code "9") (name "/HUM_T") (class "Default")
      (node (ref "J1") (pin "1") (pinfunction "1_1") (pintype "passive"))
      (node (ref "TP_HUM_T") (pin "1") (pinfunction "TP_1") (pintype "passive"))
      (node (ref "U2") (pin "3") (pinfunction "CH2_3") (pintype "input"))
    )
    (net (code "10") (name "/LCD_0") (class "Default")
      (node (ref "J6") (pin "8") (pintype "bidirectional"))
      (node (ref "U1") (pin "6") (pinfunction "E_6") (pintype "input"))
    )
    (net (code "11") (name "/LCD_1") (class "Default")
      (node (ref "J6") (pin "28") (pintype "bidirectional"))
      (node (ref "U1") (pin "5") (pinfunction "R/W_5") (pintype "input"))
    )
    (net (code "12") (name "/LCD_2") (class "Default")
      (node (ref "U1") (pin "4") (pinfunction "RS_4") (pintype "input"))
    )
    (net (code "13") (name "/LCD_4") (class "Default")
      (node (ref "J6") (pin "6") (pintype "bidirectional"))
      (node (ref "U1") (pin "11") (pinfunction "DB4_11") (pintype "bidirectional"))
    )
    (net (code "14") (name "/LCD_5") (class "Default")
      (node (ref "J6") (pin "26") (pintype "bidirectional"))
      (node (ref "U1") (pin "12") (pinfunction "DB5_12") (pintype "bidirectional"))
    )
    (net (code "15") (name "/LCD_6") (class "Default")
      (node (ref "J6") (pin "5") (pintype "bidirectional"))
      (node (ref "U1") (pin "13") (pinfunction "DB6_13") (pintype "bidirectional"))
    )
    (net (code "16") (name "/LCD_7") (class "Default")
      (node (ref "J6") (pin "25") (pintype "bidirectional"))
      (node (ref "U1") (pin "14") (pinfunction "DB7_14") (pintype "bidirectional"))
    )
    (net (code "17") (name "/LED_FALTA_AIGUA") (class "Default")
      (node (ref "J6") (pin "32") (pintype "bidirectional"))
      (node (ref "Q106") (pin "B") (pinfunction "B_B") (pintype "passive"))
      (node (ref "TP_LED_AIGUA") (pin "1") (pinfunction "TP_1") (pintype "passive"))
    )
    (net (code "18") (name "/LED_REG") (class "Default")
      (node (ref "J6") (pin "12") (pintype "bidirectional"))
      (node (ref "Q105") (pin "B") (pinfunction "B_B") (pintype "passive"))
      (node (ref "TP_LED_REG") (pin "1") (pinfunction "TP_1") (pintype "passive"))
    )
    (net (code "19") (name "/LEFT") (class "Default")
      (node (ref "J6") (pin "39") (pintype "bidirectional"))
      (node (ref "R112") (pin "1") (pinfunction "1_1") (pintype "passive"))
      (node (ref "SWLEFT") (pin "1") (pinfunction "1_1") (pintype "passive"))
    )
    (net (code "20") (name "/MISO") (class "Default")
      (node (ref "J6") (pin "34") (pintype "bidirectional"))
      (node (ref "MISO") (pin "1") (pinfunction "TP_1") (pintype "passive"))
      (node (ref "R119") (pin "1") (pinfunction "1_1") (pintype "passive"))
      (node (ref "U2") (pin "10") (pinfunction "DOUT_10") (pintype "tri_state"))
    )
    (net (code "21") (name "/MOSI") (class "Default")
      (node (ref "J6") (pin "33") (pintype "bidirectional"))
      (node (ref "MOSI") (pin "1") (pinfunction "TP_1") (pintype "passive"))
      (node (ref "R118") (pin "1") (pinfunction "1_1") (pintype "passive"))
      (node (ref "U2") (pin "9") (pinfunction "DIN_9") (pintype "input"))
    )
    (net (code "22") (name "/NTC_H") (class "Default")
      (node (ref "C101") (pin "2") (pinfunction "2_2") (pintype "passive"))
      (node (ref "J1") (pin "3") (pinfunction "3_3") (pintype "passive"))
      (node (ref "R116") (pin "1") (pinfunction "1_1") (pintype "passive"))
      (node (ref "TP_NTC_H") (pin "1") (pinfunction "TP_1") (pintype "passive"))
      (node (ref "U2") (pin "1") (pinfunction "CH0_1") (pintype "input"))
    )
    (net (code "23") (name "/NTC_T") (class "Default")
      (node (ref "C102") (pin "2") (pinfunction "2_2") (pintype "passive"))
      (node (ref "J1") (pin "2") (pinfunction "2_2") (pintype "passive"))
      (node (ref "R117") (pin "1") (pinfunction "1_1") (pintype "passive"))
      (node (ref "TP_NTC_T") (pin "1") (pinfunction "TP_1") (pintype "passive"))
      (node (ref "U2") (pin "2") (pinfunction "CH1_2") (pintype "input"))
    )
    (net (code "24") (name "/OK") (class "Default")
      (node (ref "J6") (pin "40") (pintype "bidirectional"))
      (node (ref "R110") (pin "1") (pinfunction "1_1") (pintype "passive"))
      (node (ref "SWOK") (pin "1") (pinfunction "1_1") (pintype "passive"))
    )
    (net (code "25") (name "/Persiana+") (class "Default")
      (node (ref "J3") (pin "8") (pinfunction "8_8") (pintype "passive"))
      (node (ref "K103") (pin "11") (pinfunction "11_11") (pintype "passive"))
    )
    (net (code "26") (name "/Persiana-") (class "Default")
      (node (ref "J3") (pin "7") (pinfunction "7_7") (pintype "passive"))
      (node (ref "K104") (pin "11") (pinfunction "11_11") (pintype "passive"))
    )
    (net (code "27") (name "/RELE1") (class "Default")
      (node (ref "J6") (pin "11") (pintype "bidirectional"))
      (node (ref "Q103") (pin "B") (pinfunction "B_B") (pintype "passive"))
      (node (ref "TP_RELE1") (pin "1") (pinfunction "TP_1") (pintype "passive"))
    )
    (net (code "28") (name "/RELE2") (class "Default")
      (node (ref "J6") (pin "31") (pintype "bidirectional"))
      (node (ref "Q104") (pin "B") (pinfunction "B_B") (pintype "passive"))
      (node (ref "TP_RELE2") (pin "1") (pinfunction "TP_1") (pintype "passive"))
    )
    (net (code "29") (name "/RELE3") (class "Default")
      (node (ref "J6") (pin "10") (pintype "bidirectional"))
      (node (ref "Q101") (pin "B") (pinfunction "B_B") (pintype "passive"))
      (node (ref "TP_RELE3") (pin "1") (pinfunction "TP_1") (pintype "passive"))
    )
    (net (code "30") (name "/RELE4") (class "Default")
      (node (ref "J6") (pin "30") (pintype "bidirectional"))
      (node (ref "Q102") (pin "B") (pinfunction "B_B") (pintype "passive"))
      (node (ref "TP_RELE4") (pin "1") (pinfunction "TP_1") (pintype "passive"))
    )
    (net (code "31") (name "/RIGHT") (class "Default")
      (node (ref "J6") (pin "18") (pintype "bidirectional"))
      (node (ref "R113") (pin "1") (pinfunction "1_1") (pintype "passive"))
      (node (ref "SWRIGHT") (pin "1") (pinfunction "1_1") (pintype "passive"))
    )
    (net (code "32") (name "/SCL") (class "Default")
      (node (ref "J6") (pin "4") (pintype "bidirectional"))
      (node (ref "J7") (pin "1") (pinfunction "1_1") (pintype "passive"))
    )
    (net (code "33") (name "/SDA") (class "Default")
      (node (ref "J6") (pin "24") (pintype "bidirectional"))
      (node (ref "J7") (pin "2") (pinfunction "2_2") (pintype "passive"))
    )
    (net (code "34") (name "/TRIG") (class "Default")
      (node (ref "J2") (pin "3") (pinfunction "3_3") (pintype "bidirectional"))
      (node (ref "J6") (pin "9") (pintype "bidirectional"))
      (node (ref "TP_TRIG") (pin "1") (pinfunction "TP_1") (pintype "passive"))
    )
    (net (code "35") (name "/UP") (class "Default")
      (node (ref "J6") (pin "20") (pintype "bidirectional"))
      (node (ref "R109") (pin "1") (pinfunction "1_1") (pintype "passive"))
      (node (ref "SWUP") (pin "1") (pinfunction "1_1") (pintype "passive"))
    )
    (net (code "36") (name "/Ventilador") (class "Default")
      (node (ref "J4") (pin "1") (pinfunction "1_1") (pintype "passive"))
      (node (ref "K101") (pin "11") (pinfunction "11_11") (pintype "passive"))
    )
    (net (code "37") (name "GND") (class "Default")
      (node (ref "C101") (pin "1") (pinfunction "1_1") (pintype "passive"))
      (node (ref "C102") (pin "1") (pinfunction "1_1") (pintype "passive"))
      (node (ref "C103") (pin "1") (pinfunction "1_1") (pintype "passive"))
      (node (ref "C104") (pin "1") (pinfunction "1_1") (pintype "passive"))
      (node (ref "C105") (pin "1") (pinfunction "1_1") (pintype "passive"))
      (node (ref "D103") (pin "K") (pinfunction "K_K") (pintype "passive"))
      (node (ref "D104") (pin "A") (pinfunction "A_A") (pintype "passive"))
      (node (ref "D105") (pin "A") (pinfunction "A_A") (pintype "passive"))
      (node (ref "D106") (pin "A") (pinfunction "A_A") (pintype "passive"))
      (node (ref "D107") (pin "A") (pinfunction "A_A") (pintype "passive"))
      (node (ref "J1") (pin "5") (pinfunction "5_5") (pintype "passive"))
      (node (ref "J1") (pin "6") (pinfunction "6_6") (pintype "passive"))
      (node (ref "J1") (pin "7") (pinfunction "7_7") (pintype "passive"))
      (node (ref "J1") (pin "8") (pinfunction "8_8") (pintype "passive"))
      (node (ref "J2") (pin "2") (pinfunction "2_2") (pintype "bidirectional"))
      (node (ref "J3") (pin "1") (pinfunction "1_1") (pintype "passive"))
      (node (ref "J3") (pin "2") (pinfunction "2_2") (pintype "passive"))
      (node (ref "J3") (pin "3") (pinfunction "3_3") (pintype "passive"))
      (node (ref "J3") (pin "4") (pinfunction "4_4") (pintype "passive"))
      (node (ref "J4") (pin "2") (pinfunction "2_2") (pintype "passive"))
      (node (ref "J5") (pin "2") (pinfunction "2_2") (pintype "passive"))
      (node (ref "J6") (pin "21") (pintype "bidirectional"))
      (node (ref "J6") (pin "22") (pintype "bidirectional"))
      (node (ref "J7") (pin "4") (pinfunction "4_4") (pintype "passive"))
      (node (ref "J8") (pin "2") (pinfunction "2_2") (pintype "passive"))
      (node (ref "K101") (pin "14") (pinfunction "14_14") (pintype "passive"))
      (node (ref "K101") (pin "A2") (pinfunction "A2_A2") (pintype "passive"))
      (node (ref "K102") (pin "14") (pinfunction "14_14") (pintype "passive"))
      (node (ref "K102") (pin "A2") (pinfunction "A2_A2") (pintype "passive"))
      (node (ref "K103") (pin "14") (pinfunction "14_14") (pintype "passive"))
      (node (ref "K103") (pin "A2") (pinfunction "A2_A2") (pintype "passive"))
      (node (ref "K104") (pin "14") (pinfunction "14_14") (pintype "passive"))
      (node (ref "K104") (pin "A2") (pinfunction "A2_A2") (pintype "passive"))
      (node (ref "Q105") (pin "E") (pinfunction "E_E") (pintype "passive"))
      (node (ref "Q106") (pin "E") (pinfunction "E_E") (pintype "passive"))
      (node (ref "R107") (pin "1") (pinfunction "2_1") (pintype "passive"))
      (node (ref "SWDOWN") (pin "3") (pinfunction "3_3") (pintype "passive"))
      (node (ref "SWLEFT") (pin "3") (pinfunction "3_3") (pintype "passive"))
      (node (ref "SWOK") (pin "4") (pinfunction "4_4") (pintype "passive"))
      (node (ref "SWRIGHT") (pin "3") (pinfunction "3_3") (pintype "passive"))
      (node (ref "SWUP") (pin "4") (pinfunction "4_4") (pintype "passive"))
      (node (ref "U1") (pin "1") (pinfunction "VSS_1") (pintype "power_in"))
      (node (ref "U1") (pin "10") (pinfunction "DB3_10") (pintype "bidirectional"))
      (node (ref "U1") (pin "16") (pinfunction "LEDK_16") (pintype "passive"))
      (node (ref "U1") (pin "7") (pinfunction "DB0_7") (pintype "bidirectional"))
      (node (ref "U1") (pin "8") (pinfunction "DB1_8") (pintype "bidirectional"))
      (node (ref "U1") (pin "9") (pinfunction "DB2_9") (pintype "bidirectional"))
      (node (ref "U2") (pin "12") (pinfunction "AGND_12") (pintype "power_in"))
      (node (ref "U2") (pin "4") (pinfunction "CH3_4") (pintype "input"))
      (node (ref "U2") (pin "7") (pinfunction "DGND_7") (pintype "power_in"))
    )
    (net (code "38") (name "LV+in") (class "Default")
      (node (ref "J8") (pin "1") (pinfunction "1_1") (pintype "passive"))
      (node (ref "K101") (pin "12") (pinfunction "12_12") (pintype "passive"))
      (node (ref "K102") (pin "12") (pinfunction "12_12") (pintype "passive"))
      (node (ref "K103") (pin "12") (pinfunction "12_12") (pintype "passive"))
      (node (ref "K104") (pin "12") (pinfunction "12_12") (pintype "passive"))
      (node (ref "TP_LV+in") (pin "1") (pinfunction "TP_1") (pintype "passive"))
    )
    (net (code "39") (name "Net-(D101-PadA)") (class "Default")
      (node (ref "D101") (pin "A") (pinfunction "A_A") (pintype "passive"))
      (node (ref "R105") (pin "1") (pinfunction "1_1") (pintype "passive"))
    )
    (net (code "40") (name "Net-(D101-PadK)") (class "Default")
      (node (ref "D101") (pin "K") (pinfunction "K_K") (pintype "passive"))
      (node (ref "Q105") (pin "C") (pinfunction "C_C") (pintype "passive"))
    )
    (net (code "41") (name "Net-(D102-PadA)") (class "Default")
      (node (ref "D102") (pin "A") (pinfunction "A_A") (pintype "passive"))
      (node (ref "R106") (pin "1") (pinfunction "1_1") (pintype "passive"))
    )
    (net (code "42") (name "Net-(D102-PadK)") (class "Default")
      (node (ref "D102") (pin "K") (pinfunction "K_K") (pintype "passive"))
      (node (ref "Q106") (pin "C") (pinfunction "C_C") (pintype "passive"))
    )
    (net (code "43") (name "Net-(D103-PadA)") (class "Default")
      (node (ref "D103") (pin "A") (pinfunction "A_A") (pintype "passive"))
      (node (ref "R122") (pin "1") (pinfunction "1_1") (pintype "passive"))
    )
    (net (code "44") (name "Net-(D104-PadK)") (class "Default")
      (node (ref "D104") (pin "K") (pinfunction "K_K") (pintype "passive"))
      (node (ref "K101") (pin "A1") (pinfunction "A1_A1") (pintype "passive"))
      (node (ref "Q101") (pin "E") (pinfunction "E_E") (pintype "passive"))
    )
    (net (code "45") (name "Net-(D105-PadK)") (class "Default")
      (node (ref "D105") (pin "K") (pinfunction "K_K") (pintype "passive"))
      (node (ref "K102") (pin "A1") (pinfunction "A1_A1") (pintype "passive"))
      (node (ref "Q102") (pin "E") (pinfunction "E_E") (pintype "passive"))
    )
    (net (code "46") (name "Net-(D106-PadK)") (class "Default")
      (node (ref "D106") (pin "K") (pinfunction "K_K") (pintype "passive"))
      (node (ref "K103") (pin "A1") (pinfunction "A1_A1") (pintype "passive"))
      (node (ref "Q103") (pin "E") (pinfunction "E_E") (pintype "passive"))
    )
    (net (code "47") (name "Net-(D107-PadK)") (class "Default")
      (node (ref "D107") (pin "K") (pinfunction "K_K") (pintype "passive"))
      (node (ref "K104") (pin "A1") (pinfunction "A1_A1") (pintype "passive"))
      (node (ref "Q104") (pin "E") (pinfunction "E_E") (pintype "passive"))
    )
    (net (code "48") (name "Net-(Q101-PadC)") (class "Default")
      (node (ref "Q101") (pin "C") (pinfunction "C_C") (pintype "passive"))
      (node (ref "R101") (pin "1") (pinfunction "1_1") (pintype "passive"))
    )
    (net (code "49") (name "Net-(Q102-PadC)") (class "Default")
      (node (ref "Q102") (pin "C") (pinfunction "C_C") (pintype "passive"))
      (node (ref "R102") (pin "1") (pinfunction "1_1") (pintype "passive"))
    )
    (net (code "50") (name "Net-(Q103-PadC)") (class "Default")
      (node (ref "Q103") (pin "C") (pinfunction "C_C") (pintype "passive"))
      (node (ref "R103") (pin "1") (pinfunction "1_1") (pintype "passive"))
    )
    (net (code "51") (name "Net-(Q104-PadC)") (class "Default")
      (node (ref "Q104") (pin "C") (pinfunction "C_C") (pintype "passive"))
      (node (ref "R104") (pin "1") (pinfunction "1_1") (pintype "passive"))
    )
    (net (code "52") (name "Net-(U1-LEDA)") (class "Default")
      (node (ref "R108") (pin "1") (pinfunction "1_1") (pintype "passive"))
      (node (ref "U1") (pin "15") (pinfunction "LEDA_15") (pintype "passive"))
    )
    (net (code "53") (name "Net-(U1-VO)") (class "Default")
      (node (ref "R107") (pin "3") (pinfunction "3_3") (pintype "passive"))
      (node (ref "U1") (pin "3") (pinfunction "VO_3") (pintype "passive"))
    )
    (net (code "54") (name "unconnected-(J6-Pad3)") (class "Default")
      (node (ref "J6") (pin "3") (pintype "bidirectional"))
    )
    (net (code "55") (name "unconnected-(J6-Pad7)") (class "Default")
      (node (ref "J6") (pin "7") (pintype "bidirectional"))
    )
    (net (code "56") (name "unconnected-(J6-Pad15)") (class "Default")
      (node (ref "J6") (pin "15") (pintype "bidirectional+no_connect"))
    )
    (net (code "57") (name "unconnected-(J6-Pad16)") (class "Default")
      (node (ref "J6") (pin "16") (pintype "bidirectional+no_connect"))
    )
    (net (code "58") (name "unconnected-(J6-Pad23)") (class "Default")
      (node (ref "J6") (pin "23") (pintype "bidirectional+no_connect"))
    )
    (net (code "59") (name "unconnected-(J6-Pad27)") (class "Default")
      (node (ref "J6") (pin "27") (pintype "bidirectional+no_connect"))
    )
    (net (code "60") (name "unconnected-(J6-Pad35)") (class "Default")
      (node (ref "J6") (pin "35") (pintype "bidirectional+no_connect"))
    )
    (net (code "61") (name "unconnected-(J6-Pad36)") (class "Default")
      (node (ref "J6") (pin "36") (pintype "bidirectional+no_connect"))
    )
    (net (code "62") (name "unconnected-(J6-Pad37)") (class "Default")
      (node (ref "J6") (pin "37") (pintype "bidirectional+no_connect"))
    )
    (net (code "63") (name "unconnected-(SWDOWN-Pad2)") (class "Default")
      (node (ref "SWDOWN") (pin "2") (pinfunction "2_2") (pintype "passive"))
    )
    (net (code "64") (name "unconnected-(SWDOWN-Pad4)") (class "Default")
      (node (ref "SWDOWN") (pin "4") (pinfunction "4_4") (pintype "passive"))
    )
    (net (code "65") (name "unconnected-(SWLEFT-Pad2)") (class "Default")
      (node (ref "SWLEFT") (pin "2") (pinfunction "2_2") (pintype "passive"))
    )
    (net (code "66") (name "unconnected-(SWLEFT-Pad4)") (class "Default")
      (node (ref "SWLEFT") (pin "4") (pinfunction "4_4") (pintype "passive"))
    )
    (net (code "67") (name "unconnected-(SWOK-Pad2)") (class "Default")
      (node (ref "SWOK") (pin "2") (pinfunction "2_2") (pintype "passive"))
    )
    (net (code "68") (name "unconnected-(SWOK-Pad3)") (class "Default")
      (node (ref "SWOK") (pin "3") (pinfunction "3_3") (pintype "passive"))
    )
    (net (code "69") (name "unconnected-(SWRIGHT-Pad2)") (class "Default")
      (node (ref "SWRIGHT") (pin "2") (pinfunction "2_2") (pintype "passive"))
    )
    (net (code "70") (name "unconnected-(SWRIGHT-Pad4)") (class "Default")
      (node (ref "SWRIGHT") (pin "4") (pinfunction "4_4") (pintype "passive"))
    )
    (net (code "71") (name "unconnected-(SWUP-Pad2)") (class "Default")
      (node (ref "SWUP") (pin "2") (pinfunction "2_2") (pintype "passive"))
    )
    (net (code "72") (name "unconnected-(SWUP-Pad3)") (class "Default")
      (node (ref "SWUP") (pin "3") (pinfunction "3_3") (pintype "passive"))
    )
    (net (code "73") (name "unconnected-(U2-NC-Pad5)") (class "Default")
      (node (ref "U2") (pin "5") (pinfunction "NC_5") (pintype "passive"))
    )
    (net (code "74") (name "unconnected-(U2-NC-Pad6)") (class "Default")
      (node (ref "U2") (pin "6") (pinfunction "NC_6") (pintype "passive"))
    )
  )
)
